# IMU_ACC.net
KiCad netlist of a schematic drawn in Altium Designer
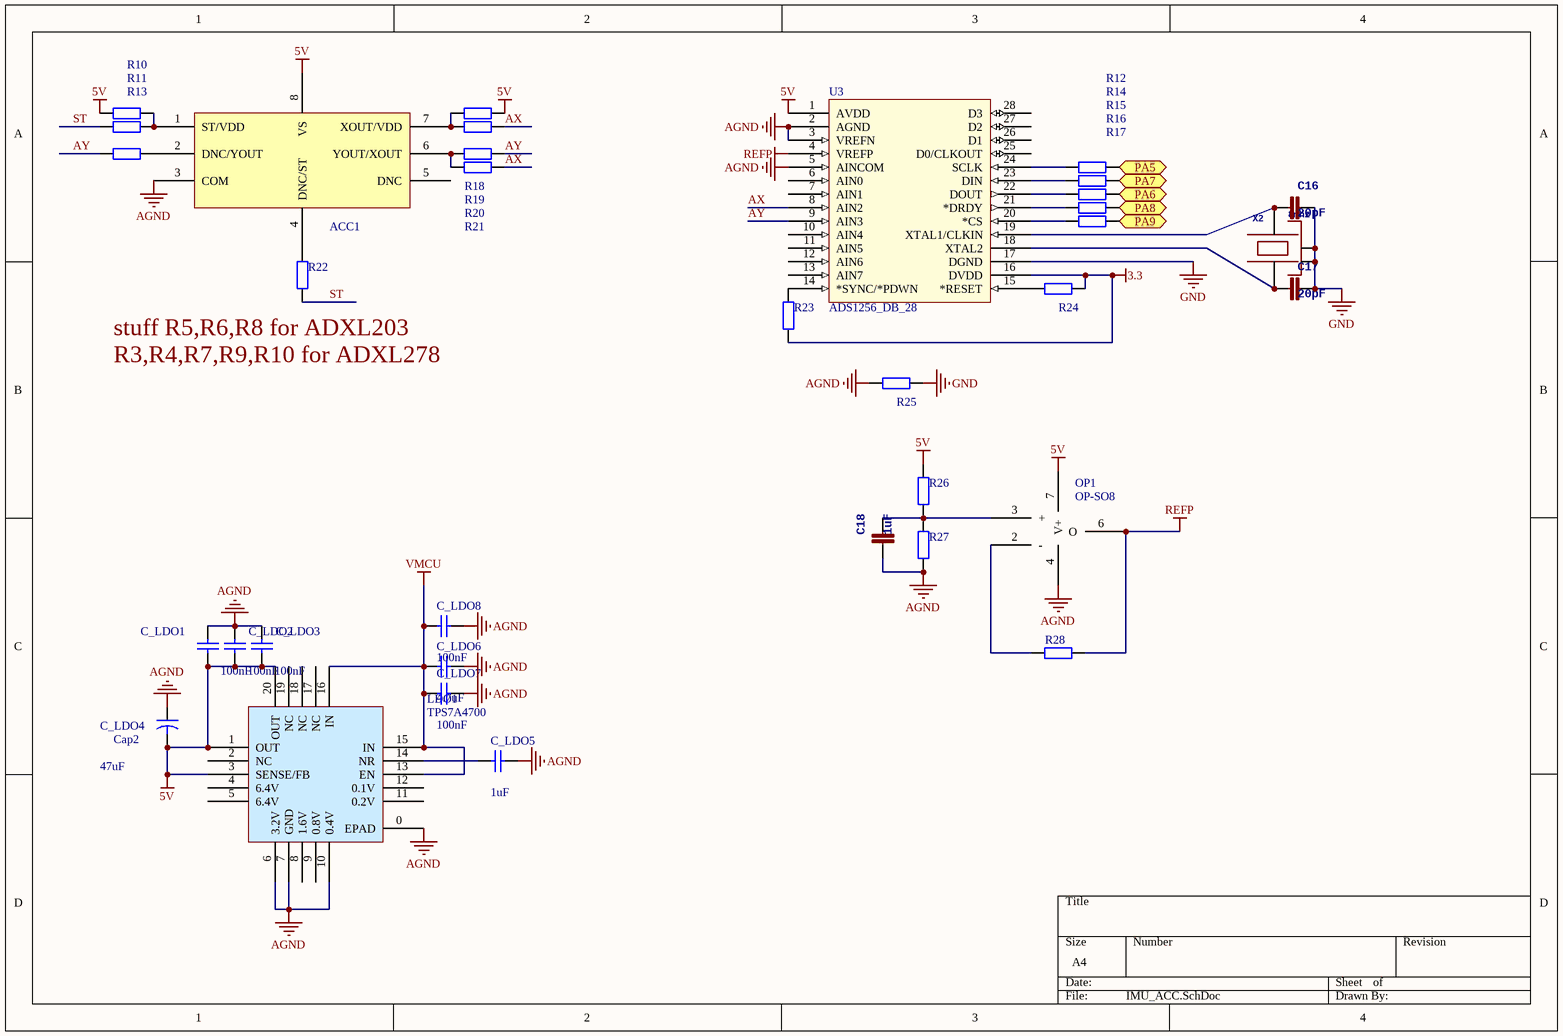
[diagram p0: IMU_ACC.SchDoc]

(export (version "E")
  (design (tool "Eeschema 10.0.6"))
  (components
    (comp (ref "ACC1")
      (value "ACC-8")
      (footprint "ADXL203")
      (description "Imported")
      (libsource (lib "advsensor") (part "ACC-8"))
    )
    (comp (ref "C16")
      (value "20pF")
      (footprint "0402")
      (description "电容")
      (fields (field (name "PARTNO") "CC0402ZRY5V7BB104"))
      (libsource (lib "") (part "CAP0402-CAP_1"))
    )
    (comp (ref "C17")
      (value "20pF")
      (footprint "0402")
      (description "电容")
      (fields (field (name "PARTNO") "CC0402ZRY5V7BB104"))
      (libsource (lib "") (part "CAP0402-CAP_1"))
    )
    (comp (ref "C18")
      (value "1uF")
      (footprint "0603")
      (description "电容")
      (fields (field (name "PARTNO") "CC0402ZRY5V7BB104"))
      (libsource (lib "mcu_board") (part "CAP0402-CAP"))
    )
    (comp (ref "C_LDO1")
      (value "100nF")
      (footprint "0603")
      (description "Capacitor")
      (fields (field (name "PUBLISHER") "Altium Limited"))
      (libsource (lib "Miscellaneous Devices") (part "Cap"))
    )
    (comp (ref "C_LDO2")
      (value "100nF")
      (footprint "0603")
      (description "Capacitor")
      (fields (field (name "PUBLISHER") "Altium Limited"))
      (libsource (lib "Miscellaneous Devices") (part "Cap"))
    )
    (comp (ref "C_LDO3")
      (value "100nF")
      (footprint "0603")
      (description "Capacitor")
      (fields (field (name "PUBLISHER") "Altium Limited"))
      (libsource (lib "Miscellaneous Devices") (part "Cap"))
    )
    (comp (ref "C_LDO4")
      (value "Cap2")
      (footprint "1210")
      (description "Capacitor")
      (fields (field (name "ALTIUM_VALUE") "47uF") (field (name "PUBLISHER") "Altium Limited"))
      (libsource (lib "Miscellaneous Devices") (part "Cap2"))
    )
    (comp (ref "C_LDO5")
      (value "1uF")
      (footprint "0603")
      (description "Capacitor")
      (fields (field (name "PUBLISHER") "Altium Limited"))
      (libsource (lib "Miscellaneous Devices") (part "Cap"))
    )
    (comp (ref "C_LDO6")
      (value "4.7uF")
      (footprint "0603")
      (description "Capacitor")
      (fields (field (name "PUBLISHER") "Altium Limited"))
      (libsource (lib "Miscellaneous Devices") (part "Cap"))
    )
    (comp (ref "C_LDO7")
      (value "100nF")
      (footprint "0603")
      (description "Capacitor")
      (fields (field (name "PUBLISHER") "Altium Limited"))
      (libsource (lib "Miscellaneous Devices") (part "Cap"))
    )
    (comp (ref "C_LDO8")
      (value "100nF")
      (footprint "1210")
      (description "Capacitor")
      (fields (field (name "PUBLISHER") "Altium Limited"))
      (libsource (lib "Miscellaneous Devices") (part "Cap"))
    )
    (comp (ref "LDO1")
      (value "TPS7A4700")
      (footprint "TPS7A4700 - b")
      (libsource (lib "advsensor") (part "TPS7A4700"))
    )
    (comp (ref "OP1") (value "OP-SO8") (footprint "D8") (libsource (lib "sch") (part "OP-SO8")))
    (comp (ref "R10")
      (value "~")
      (footprint "0402")
      (description "Resistor")
      (fields (field (name "PUBLISHER") "Altium Limited"))
      (libsource (lib "Miscellaneous Devices") (part "Res2"))
    )
    (comp (ref "R11")
      (value "~")
      (footprint "0402")
      (description "Resistor")
      (fields (field (name "PUBLISHER") "Altium Limited"))
      (libsource (lib "Miscellaneous Devices") (part "Res2"))
    )
    (comp (ref "R12")
      (value "~")
      (footprint "0402")
      (description "Resistor")
      (fields (field (name "PUBLISHER") "Altium Limited"))
      (libsource (lib "Miscellaneous Devices") (part "Res2"))
    )
    (comp (ref "R13")
      (value "~")
      (footprint "0402")
      (description "Resistor")
      (fields (field (name "PUBLISHER") "Altium Limited"))
      (libsource (lib "Miscellaneous Devices") (part "Res2"))
    )
    (comp (ref "R14")
      (value "~")
      (footprint "0402")
      (description "Resistor")
      (fields (field (name "PUBLISHER") "Altium Limited"))
      (libsource (lib "Miscellaneous Devices") (part "Res2"))
    )
    (comp (ref "R15")
      (value "~")
      (footprint "0402")
      (description "Resistor")
      (fields (field (name "PUBLISHER") "Altium Limited"))
      (libsource (lib "Miscellaneous Devices") (part "Res2"))
    )
    (comp (ref "R16")
      (value "~")
      (footprint "0402")
      (description "Resistor")
      (fields (field (name "PUBLISHER") "Altium Limited"))
      (libsource (lib "Miscellaneous Devices") (part "Res2"))
    )
    (comp (ref "R17")
      (value "~")
      (footprint "0402")
      (description "Resistor")
      (fields (field (name "PUBLISHER") "Altium Limited"))
      (libsource (lib "Miscellaneous Devices") (part "Res2"))
    )
    (comp (ref "R18")
      (value "~")
      (footprint "0402")
      (description "Resistor")
      (fields (field (name "PUBLISHER") "Altium Limited"))
      (libsource (lib "Miscellaneous Devices") (part "Res2"))
    )
    (comp (ref "R19")
      (value "~")
      (footprint "0402")
      (description "Resistor")
      (fields (field (name "PUBLISHER") "Altium Limited"))
      (libsource (lib "Miscellaneous Devices") (part "Res2"))
    )
    (comp (ref "R20")
      (value "~")
      (footprint "0402")
      (description "Resistor")
      (fields (field (name "PUBLISHER") "Altium Limited"))
      (libsource (lib "Miscellaneous Devices") (part "Res2"))
    )
    (comp (ref "R21")
      (value "~")
      (footprint "0402")
      (description "Resistor")
      (fields (field (name "PUBLISHER") "Altium Limited"))
      (libsource (lib "Miscellaneous Devices") (part "Res2"))
    )
    (comp (ref "R22")
      (value "~")
      (footprint "0402")
      (description "Resistor")
      (fields (field (name "PUBLISHER") "Altium Limited"))
      (libsource (lib "") (part "Res2_2"))
    )
    (comp (ref "R23")
      (value "~")
      (footprint "0402")
      (description "Resistor")
      (fields (field (name "PUBLISHER") "Altium Limited"))
      (libsource (lib "") (part "Res2_1"))
    )
    (comp (ref "R24")
      (value "~")
      (footprint "0402")
      (description "Resistor")
      (fields (field (name "PUBLISHER") "Altium Limited"))
      (libsource (lib "Miscellaneous Devices") (part "Res2"))
    )
    (comp (ref "R25")
      (value "~")
      (footprint "0402")
      (description "Resistor")
      (fields (field (name "PUBLISHER") "Altium Limited"))
      (libsource (lib "Miscellaneous Devices") (part "Res2"))
    )
    (comp (ref "R26")
      (value "~")
      (footprint "0603")
      (description "Resistor")
      (fields (field (name "PUBLISHER") "Altium Limited"))
      (libsource (lib "") (part "Res2_2"))
    )
    (comp (ref "R27")
      (value "~")
      (footprint "0603")
      (description "Resistor")
      (fields (field (name "PUBLISHER") "Altium Limited"))
      (libsource (lib "") (part "Res2_2"))
    )
    (comp (ref "R28")
      (value "~")
      (footprint "0402")
      (description "Resistor")
      (fields (field (name "PUBLISHER") "Altium Limited"))
      (libsource (lib "") (part "Res2_3"))
    )
    (comp (ref "U3")
      (value "ADS1256_DB_28")
      (footprint "DB28-L")
      (description "Imported")
      (fields
        (field (name "MANUFACTURER") "Texas Instruments")
        (field (name "GENERIC_PART_NUMBER") "ADS1256")
      )
      (libsource (lib "advsensor") (part "ADS1256_DB_28"))
    )
    (comp (ref "X2")
      (value "8mhz")
      (footprint "OSCILLATOR-3.2X2.5")
      (description "Crystal Oscillator in 3.2x2.5 SMD")
      (libsource (lib "sch") (part "OSCILLATOR-3.2X2.5"))
    )
  )
  (nets
    (net (code "1") (name "/AX") (class "Default")
      (node (ref "R19") (pin "2") (pinfunction "2_2") (pintype "passive"))
      (node (ref "R21") (pin "2") (pinfunction "2_2") (pintype "passive"))
      (node (ref "U3") (pin "8") (pinfunction "AIN2_8") (pintype "input"))
    )
    (net (code "2") (name "/AY") (class "Default")
      (node (ref "R13") (pin "1") (pinfunction "1_1") (pintype "passive"))
      (node (ref "R20") (pin "2") (pinfunction "2_2") (pintype "passive"))
      (node (ref "U3") (pin "9") (pinfunction "AIN3_9") (pintype "input"))
    )
    (net (code "3") (name "/PA5") (class "Default")
      (node (ref "R12") (pin "2") (pinfunction "2_2") (pintype "passive"))
    )
    (net (code "4") (name "/PA6") (class "Default")
      (node (ref "R15") (pin "2") (pinfunction "2_2") (pintype "passive"))
    )
    (net (code "5") (name "/PA7") (class "Default")
      (node (ref "R14") (pin "2") (pinfunction "2_2") (pintype "passive"))
    )
    (net (code "6") (name "/PA8") (class "Default")
      (node (ref "R16") (pin "2") (pinfunction "2_2") (pintype "passive"))
    )
    (net (code "7") (name "/PA9") (class "Default")
      (node (ref "R17") (pin "2") (pinfunction "2_2") (pintype "passive"))
    )
    (net (code "8") (name "/ST") (class "Default")
      (node (ref "R11") (pin "1") (pinfunction "1_1") (pintype "passive"))
      (node (ref "R22") (pin "1") (pinfunction "1_1") (pintype "passive"))
    )
    (net (code "9") (name "3.3") (class "Default")
      (node (ref "R23") (pin "2") (pinfunction "2_2") (pintype "passive"))
      (node (ref "R24") (pin "2") (pinfunction "2_2") (pintype "passive"))
      (node (ref "U3") (pin "16") (pinfunction "DVDD_16") (pintype "power_in"))
    )
    (net (code "10") (name "5V") (class "Default")
      (node (ref "ACC1") (pin "8") (pinfunction "VS_8") (pintype "passive"))
      (node (ref "C_LDO1") (pin "2") (pinfunction "2_2") (pintype "passive"))
      (node (ref "C_LDO2") (pin "2") (pinfunction "2_2") (pintype "passive"))
      (node (ref "C_LDO3") (pin "2") (pinfunction "2_2") (pintype "passive"))
      (node (ref "C_LDO4") (pin "2") (pinfunction "2_2") (pintype "passive"))
      (node (ref "LDO1") (pin "1") (pinfunction "OUT_1") (pintype "passive"))
      (node (ref "LDO1") (pin "20") (pinfunction "OUT_20") (pintype "passive"))
      (node (ref "LDO1") (pin "3") (pinfunction "SENSE/FB_3") (pintype "passive"))
      (node (ref "OP1") (pin "7") (pinfunction "V+_7") (pintype "passive"))
      (node (ref "R10") (pin "1") (pinfunction "1_1") (pintype "passive"))
      (node (ref "R18") (pin "2") (pinfunction "2_2") (pintype "passive"))
      (node (ref "R26") (pin "2") (pinfunction "2_2") (pintype "passive"))
      (node (ref "U3") (pin "1") (pinfunction "AVDD_1") (pintype "power_in"))
    )
    (net (code "11") (name "AGND") (class "Default")
      (node (ref "ACC1") (pin "3") (pinfunction "COM_3") (pintype "passive"))
      (node (ref "C18") (pin "2") (pinfunction "2_2") (pintype "passive"))
      (node (ref "C_LDO1") (pin "1") (pinfunction "1_1") (pintype "passive"))
      (node (ref "C_LDO2") (pin "1") (pinfunction "1_1") (pintype "passive"))
      (node (ref "C_LDO3") (pin "1") (pinfunction "1_1") (pintype "passive"))
      (node (ref "C_LDO4") (pin "1") (pinfunction "1_1") (pintype "passive"))
      (node (ref "C_LDO5") (pin "1") (pinfunction "1_1") (pintype "passive"))
      (node (ref "C_LDO6") (pin "2") (pinfunction "2_2") (pintype "passive"))
      (node (ref "C_LDO7") (pin "2") (pinfunction "2_2") (pintype "passive"))
      (node (ref "C_LDO8") (pin "2") (pinfunction "2_2") (pintype "passive"))
      (node (ref "LDO1") (pin "0") (pinfunction "EPAD_0") (pintype "passive"))
      (node (ref "LDO1") (pin "10") (pinfunction "0.4V_10") (pintype "passive"))
      (node (ref "LDO1") (pin "6") (pinfunction "3.2V_6") (pintype "passive"))
      (node (ref "LDO1") (pin "7") (pinfunction "GND_7") (pintype "passive"))
      (node (ref "OP1") (pin "4") (pinfunction "5_4") (pintype "passive"))
      (node (ref "R25") (pin "1") (pinfunction "1_1") (pintype "passive"))
      (node (ref "R27") (pin "1") (pinfunction "1_1") (pintype "passive"))
      (node (ref "U3") (pin "2") (pinfunction "AGND_2") (pintype "power_in"))
      (node (ref "U3") (pin "3") (pinfunction "VREFN_3") (pintype "input"))
      (node (ref "U3") (pin "5") (pinfunction "AINCOM_5") (pintype "input"))
    )
    (net (code "12") (name "GND") (class "Default")
      (node (ref "C16") (pin "1") (pinfunction "1_1") (pintype "passive"))
      (node (ref "C17") (pin "1") (pinfunction "1_1") (pintype "passive"))
      (node (ref "R25") (pin "2") (pinfunction "2_2") (pintype "passive"))
      (node (ref "U3") (pin "17") (pinfunction "DGND_17") (pintype "power_in"))
      (node (ref "X2") (pin "2") (pinfunction "NC_2_2") (pintype "open_emitter"))
      (node (ref "X2") (pin "4") (pinfunction "NC_4_4") (pintype "open_emitter"))
    )
    (net (code "13") (name "Net-(ACC1-DNC{slash}ST)") (class "Default")
      (node (ref "ACC1") (pin "4") (pinfunction "DNC/ST_4") (pintype "passive"))
      (node (ref "R22") (pin "2") (pinfunction "2_2") (pintype "passive"))
    )
    (net (code "14") (name "Net-(ACC1-DNC{slash}YOUT)") (class "Default")
      (node (ref "ACC1") (pin "2") (pinfunction "DNC/YOUT_2") (pintype "passive"))
      (node (ref "R13") (pin "2") (pinfunction "2_2") (pintype "passive"))
    )
    (net (code "15") (name "Net-(ACC1-ST{slash}VDD)") (class "Default")
      (node (ref "ACC1") (pin "1") (pinfunction "ST/VDD_1") (pintype "passive"))
      (node (ref "R10") (pin "2") (pinfunction "2_2") (pintype "passive"))
      (node (ref "R11") (pin "2") (pinfunction "2_2") (pintype "passive"))
    )
    (net (code "16") (name "Net-(ACC1-XOUT{slash}VDD)") (class "Default")
      (node (ref "ACC1") (pin "7") (pinfunction "XOUT/VDD_7") (pintype "passive"))
      (node (ref "R18") (pin "1") (pinfunction "1_1") (pintype "passive"))
      (node (ref "R19") (pin "1") (pinfunction "1_1") (pintype "passive"))
    )
    (net (code "17") (name "Net-(ACC1-YOUT{slash}XOUT)") (class "Default")
      (node (ref "ACC1") (pin "6") (pinfunction "YOUT/XOUT_6") (pintype "passive"))
      (node (ref "R20") (pin "1") (pinfunction "1_1") (pintype "passive"))
      (node (ref "R21") (pin "1") (pinfunction "1_1") (pintype "passive"))
    )
    (net (code "18") (name "Net-(LDO1-NR)") (class "Default")
      (node (ref "C_LDO5") (pin "2") (pinfunction "2_2") (pintype "passive"))
      (node (ref "LDO1") (pin "14") (pinfunction "NR_14") (pintype "passive"))
    )
    (net (code "19") (name "Net-(OP1-+)") (class "Default")
      (node (ref "C18") (pin "1") (pinfunction "1_1") (pintype "passive"))
      (node (ref "OP1") (pin "3") (pinfunction "+_3") (pintype "passive"))
      (node (ref "R26") (pin "1") (pinfunction "1_1") (pintype "passive"))
      (node (ref "R27") (pin "2") (pinfunction "2_2") (pintype "passive"))
    )
    (net (code "20") (name "Net-(OP1--)") (class "Default")
      (node (ref "OP1") (pin "2") (pinfunction "-_2") (pintype "passive"))
      (node (ref "R28") (pin "2") (pinfunction "2_2") (pintype "passive"))
    )
    (net (code "21") (name "Net-(U3-*CS)") (class "Default")
      (node (ref "R17") (pin "1") (pinfunction "1_1") (pintype "passive"))
      (node (ref "U3") (pin "20") (pinfunction "*CS_20") (pintype "input"))
    )
    (net (code "22") (name "Net-(U3-*DRDY)") (class "Default")
      (node (ref "R16") (pin "1") (pinfunction "1_1") (pintype "passive"))
      (node (ref "U3") (pin "21") (pinfunction "*DRDY_21") (pintype "output"))
    )
    (net (code "23") (name "Net-(U3-*RESET)") (class "Default")
      (node (ref "R24") (pin "1") (pinfunction "1_1") (pintype "passive"))
      (node (ref "U3") (pin "15") (pinfunction "*RESET_15") (pintype "input"))
    )
    (net (code "24") (name "Net-(U3-*SYNC{slash}*PDWN)") (class "Default")
      (node (ref "R23") (pin "1") (pinfunction "1_1") (pintype "passive"))
      (node (ref "U3") (pin "14") (pinfunction "*SYNC/*PDWN_14") (pintype "input"))
    )
    (net (code "25") (name "Net-(U3-DIN)") (class "Default")
      (node (ref "R14") (pin "1") (pinfunction "1_1") (pintype "passive"))
      (node (ref "U3") (pin "23") (pinfunction "DIN_23") (pintype "input"))
    )
    (net (code "26") (name "Net-(U3-DOUT)") (class "Default")
      (node (ref "R15") (pin "1") (pinfunction "1_1") (pintype "passive"))
      (node (ref "U3") (pin "22") (pinfunction "DOUT_22") (pintype "output"))
    )
    (net (code "27") (name "Net-(U3-SCLK)") (class "Default")
      (node (ref "R12") (pin "1") (pinfunction "1_1") (pintype "passive"))
      (node (ref "U3") (pin "24") (pinfunction "SCLK_24") (pintype "input"))
    )
    (net (code "28") (name "Net-(U3-XTAL1{slash}CLKIN)") (class "Default")
      (node (ref "C16") (pin "2") (pinfunction "2_2") (pintype "passive"))
      (node (ref "U3") (pin "19") (pinfunction "XTAL1/CLKIN_19") (pintype "input"))
      (node (ref "X2") (pin "3") (pinfunction "3_3") (pintype "passive"))
    )
    (net (code "29") (name "Net-(U3-XTAL2)") (class "Default")
      (node (ref "C17") (pin "2") (pinfunction "2_2") (pintype "passive"))
      (node (ref "U3") (pin "18") (pinfunction "XTAL2_18") (pintype "passive"))
      (node (ref "X2") (pin "1") (pinfunction "1_1") (pintype "passive"))
    )
    (net (code "30") (name "REFP") (class "Default")
      (node (ref "OP1") (pin "6") (pinfunction "O_6") (pintype "passive"))
      (node (ref "R28") (pin "1") (pinfunction "1_1") (pintype "passive"))
      (node (ref "U3") (pin "4") (pinfunction "VREFP_4") (pintype "input"))
    )
    (net (code "31") (name "VMCU") (class "Default")
      (node (ref "C_LDO6") (pin "1") (pinfunction "1_1") (pintype "passive"))
      (node (ref "C_LDO7") (pin "1") (pinfunction "1_1") (pintype "passive"))
      (node (ref "C_LDO8") (pin "1") (pinfunction "1_1") (pintype "passive"))
      (node (ref "LDO1") (pin "13") (pinfunction "EN_13") (pintype "passive"))
      (node (ref "LDO1") (pin "15") (pinfunction "IN_15") (pintype "passive"))
      (node (ref "LDO1") (pin "16") (pinfunction "IN_16") (pintype "passive"))
    )
    (net (code "32") (name "unconnected-(ACC1-DNC-Pad5)") (class "Default")
      (node (ref "ACC1") (pin "5") (pinfunction "DNC_5") (pintype "passive"))
    )
    (net (code "33") (name "unconnected-(LDO1-0.1V-Pad12)") (class "Default")
      (node (ref "LDO1") (pin "12") (pinfunction "0.1V_12") (pintype "passive"))
    )
    (net (code "34") (name "unconnected-(LDO1-0.2V-Pad11)") (class "Default")
      (node (ref "LDO1") (pin "11") (pinfunction "0.2V_11") (pintype "passive"))
    )
    (net (code "35") (name "unconnected-(LDO1-0.8V-Pad9)") (class "Default")
      (node (ref "LDO1") (pin "9") (pinfunction "0.8V_9") (pintype "passive"))
    )
    (net (code "36") (name "unconnected-(LDO1-1.6V-Pad8)") (class "Default")
      (node (ref "LDO1") (pin "8") (pinfunction "1.6V_8") (pintype "passive"))
    )
    (net (code "37") (name "unconnected-(LDO1-6.4V-Pad4)") (class "Default")
      (node (ref "LDO1") (pin "4") (pinfunction "6.4V_4") (pintype "passive"))
    )
    (net (code "38") (name "unconnected-(LDO1-6.4V-Pad5)") (class "Default")
      (node (ref "LDO1") (pin "5") (pinfunction "6.4V_5") (pintype "passive"))
    )
    (net (code "39") (name "unconnected-(LDO1-NC-Pad2)") (class "Default")
      (node (ref "LDO1") (pin "2") (pinfunction "NC_2") (pintype "passive"))
    )
    (net (code "40") (name "unconnected-(LDO1-NC-Pad17)") (class "Default")
      (node (ref "LDO1") (pin "17") (pinfunction "NC_17") (pintype "passive"))
    )
    (net (code "41") (name "unconnected-(LDO1-NC-Pad18)") (class "Default")
      (node (ref "LDO1") (pin "18") (pinfunction "NC_18") (pintype "passive"))
    )
    (net (code "42") (name "unconnected-(LDO1-NC-Pad19)") (class "Default")
      (node (ref "LDO1") (pin "19") (pinfunction "NC_19") (pintype "passive"))
    )
    (net (code "43") (name "unconnected-(U3-AIN0-Pad6)") (class "Default")
      (node (ref "U3") (pin "6") (pinfunction "AIN0_6") (pintype "input"))
    )
    (net (code "44") (name "unconnected-(U3-AIN1-Pad7)") (class "Default")
      (node (ref "U3") (pin "7") (pinfunction "AIN1_7") (pintype "input"))
    )
    (net (code "45") (name "unconnected-(U3-AIN4-Pad10)") (class "Default")
      (node (ref "U3") (pin "10") (pinfunction "AIN4_10") (pintype "input"))
    )
    (net (code "46") (name "unconnected-(U3-AIN5-Pad11)") (class "Default")
      (node (ref "U3") (pin "11") (pinfunction "AIN5_11") (pintype "input"))
    )
    (net (code "47") (name "unconnected-(U3-AIN6-Pad12)") (class "Default")
      (node (ref "U3") (pin "12") (pinfunction "AIN6_12") (pintype "input"))
    )
    (net (code "48") (name "unconnected-(U3-AIN7-Pad13)") (class "Default")
      (node (ref "U3") (pin "13") (pinfunction "AIN7_13") (pintype "input"))
    )
    (net (code "49") (name "unconnected-(U3-D0{slash}CLKOUT-Pad25)") (class "Default")
      (node (ref "U3") (pin "25") (pinfunction "D0/CLKOUT_25") (pintype "bidirectional"))
    )
    (net (code "50") (name "unconnected-(U3-D1-Pad26)") (class "Default")
      (node (ref "U3") (pin "26") (pinfunction "D1_26") (pintype "bidirectional"))
    )
    (net (code "51") (name "unconnected-(U3-D2-Pad27)") (class "Default")
      (node (ref "U3") (pin "27") (pinfunction "D2_27") (pintype "bidirectional"))
    )
    (net (code "52") (name "unconnected-(U3-D3-Pad28)") (class "Default")
      (node (ref "U3") (pin "28") (pinfunction "D3_28") (pintype "bidirectional"))
    )
  )
)
